# touch-sensor.net
KiCad netlist of a schematic drawn in EAGLE
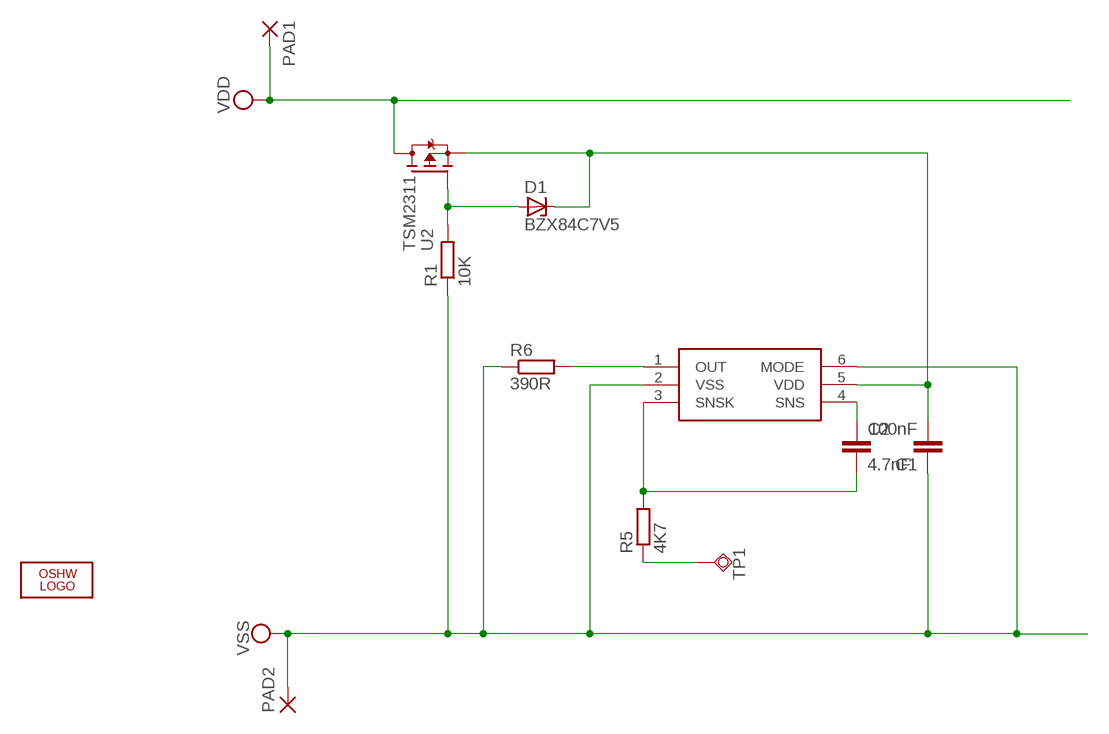
[diagram p0: schematic, sheet 1]

(export (version "E")
  (design (tool "Eeschema 10.0.6"))
  (components
    (comp (ref "C1")
      (value "100nF")
      (footprint "eagle-import:C0603")
      (libsource (lib "eagle-import") (part "C-EUC0603"))
    )
    (comp (ref "C2")
      (value "4.7nF")
      (footprint "eagle-import:C0603")
      (libsource (lib "eagle-import") (part "C-EUC0603"))
    )
    (comp (ref "D1")
      (value "BZX84C7V5")
      (footprint "eagle-import:SOT23")
      (libsource (lib "eagle-import") (part "BZX84C"))
    )
    (comp (ref "LOGO1")
      (value "OSHW_LOGO_10MILX0200-NT")
      (footprint "eagle-import:OSHW_10X200_NOTEXT")
      (libsource (lib "eagle-import") (part "OSHW_LOGO_10MILX0200-NT"))
    )
    (comp (ref "PAD1")
      (value "3,81/1,3")
      (footprint "eagle-import:3,81_1,3")
      (libsource (lib "eagle-import") (part "3,81/1,3"))
    )
    (comp (ref "PAD2")
      (value "3,81/1,3")
      (footprint "eagle-import:3,81_1,3")
      (libsource (lib "eagle-import") (part "3,81/1,3"))
    )
    (comp (ref "R1")
      (value "10K")
      (footprint "eagle-import:R0603")
      (libsource (lib "eagle-import") (part "R-EU_R0603"))
    )
    (comp (ref "R5")
      (value "4K7")
      (footprint "eagle-import:R0603")
      (libsource (lib "eagle-import") (part "R-EU_R0603"))
    )
    (comp (ref "R6")
      (value "390R")
      (footprint "eagle-import:R0603")
      (libsource (lib "eagle-import") (part "R-EU_R0603"))
    )
    (comp (ref "TP1")
      (value "TPSQTP20SQ")
      (footprint "eagle-import:TP20SQ")
      (libsource (lib "eagle-import") (part "TPSQTP20SQ"))
    )
    (comp (ref "U1")
      (value "AT42QT1011")
      (footprint "eagle-import:SOT23-6")
      (libsource (lib "eagle-import") (part "AT42QT1011"))
    )
    (comp (ref "U2")
      (value "TSM2311")
      (footprint "eagle-import:SOT23")
      (libsource (lib "eagle-import") (part "TSM2311"))
    )
  )
  (nets
    (net (code "1") (name "Net-(D1-A)") (class "Default")
      (node (ref "D1") (pin "1") (pinfunction "A_1") (pintype "passive"))
      (node (ref "R1") (pin "2") (pinfunction "2_2") (pintype "passive"))
      (node (ref "U2") (pin "1") (pinfunction "G_1") (pintype "passive"))
    )
    (net (code "2") (name "Net-(D1-C)") (class "Default")
      (node (ref "C1") (pin "2") (pinfunction "2_2") (pintype "passive"))
      (node (ref "D1") (pin "3") (pinfunction "C_3") (pintype "passive"))
      (node (ref "U1") (pin "5") (pinfunction "VDD_5") (pintype "bidirectional"))
      (node (ref "U2") (pin "2") (pinfunction "S_2") (pintype "passive"))
    )
    (net (code "3") (name "Net-(R5-Pad1)") (class "Default")
      (node (ref "R5") (pin "1") (pinfunction "1_1") (pintype "passive"))
      (node (ref "TP1") (pin "TP") (pinfunction "TP_TP") (pintype "input"))
    )
    (net (code "4") (name "Net-(U1-OUT)") (class "Default")
      (node (ref "R6") (pin "2") (pinfunction "2_2") (pintype "passive"))
      (node (ref "U1") (pin "1") (pinfunction "OUT_1") (pintype "bidirectional"))
    )
    (net (code "5") (name "Net-(U1-SNS)") (class "Default")
      (node (ref "C2") (pin "1") (pinfunction "1_1") (pintype "passive"))
      (node (ref "U1") (pin "4") (pinfunction "SNS_4") (pintype "bidirectional"))
    )
    (net (code "6") (name "Net-(U1-SNSK)") (class "Default")
      (node (ref "C2") (pin "2") (pinfunction "2_2") (pintype "passive"))
      (node (ref "R5") (pin "2") (pinfunction "2_2") (pintype "passive"))
      (node (ref "U1") (pin "3") (pinfunction "SNSK_3") (pintype "bidirectional"))
    )
    (net (code "7") (name "VDD") (class "Default")
      (node (ref "PAD1") (pin "1") (pinfunction "P_1") (pintype "passive"))
      (node (ref "U2") (pin "3") (pinfunction "D_3") (pintype "passive"))
    )
    (net (code "8") (name "VSS") (class "Default")
      (node (ref "C1") (pin "1") (pinfunction "1_1") (pintype "passive"))
      (node (ref "PAD2") (pin "1") (pinfunction "P_1") (pintype "passive"))
      (node (ref "R1") (pin "1") (pinfunction "1_1") (pintype "passive"))
      (node (ref "R6") (pin "1") (pinfunction "1_1") (pintype "passive"))
      (node (ref "U1") (pin "2") (pinfunction "VSS_2") (pintype "bidirectional"))
      (node (ref "U1") (pin "6") (pinfunction "MODE_6") (pintype "bidirectional"))
    )
  )
)
